# Adafruit_MPU6050.net
KiCad netlist of a schematic drawn in EAGLE
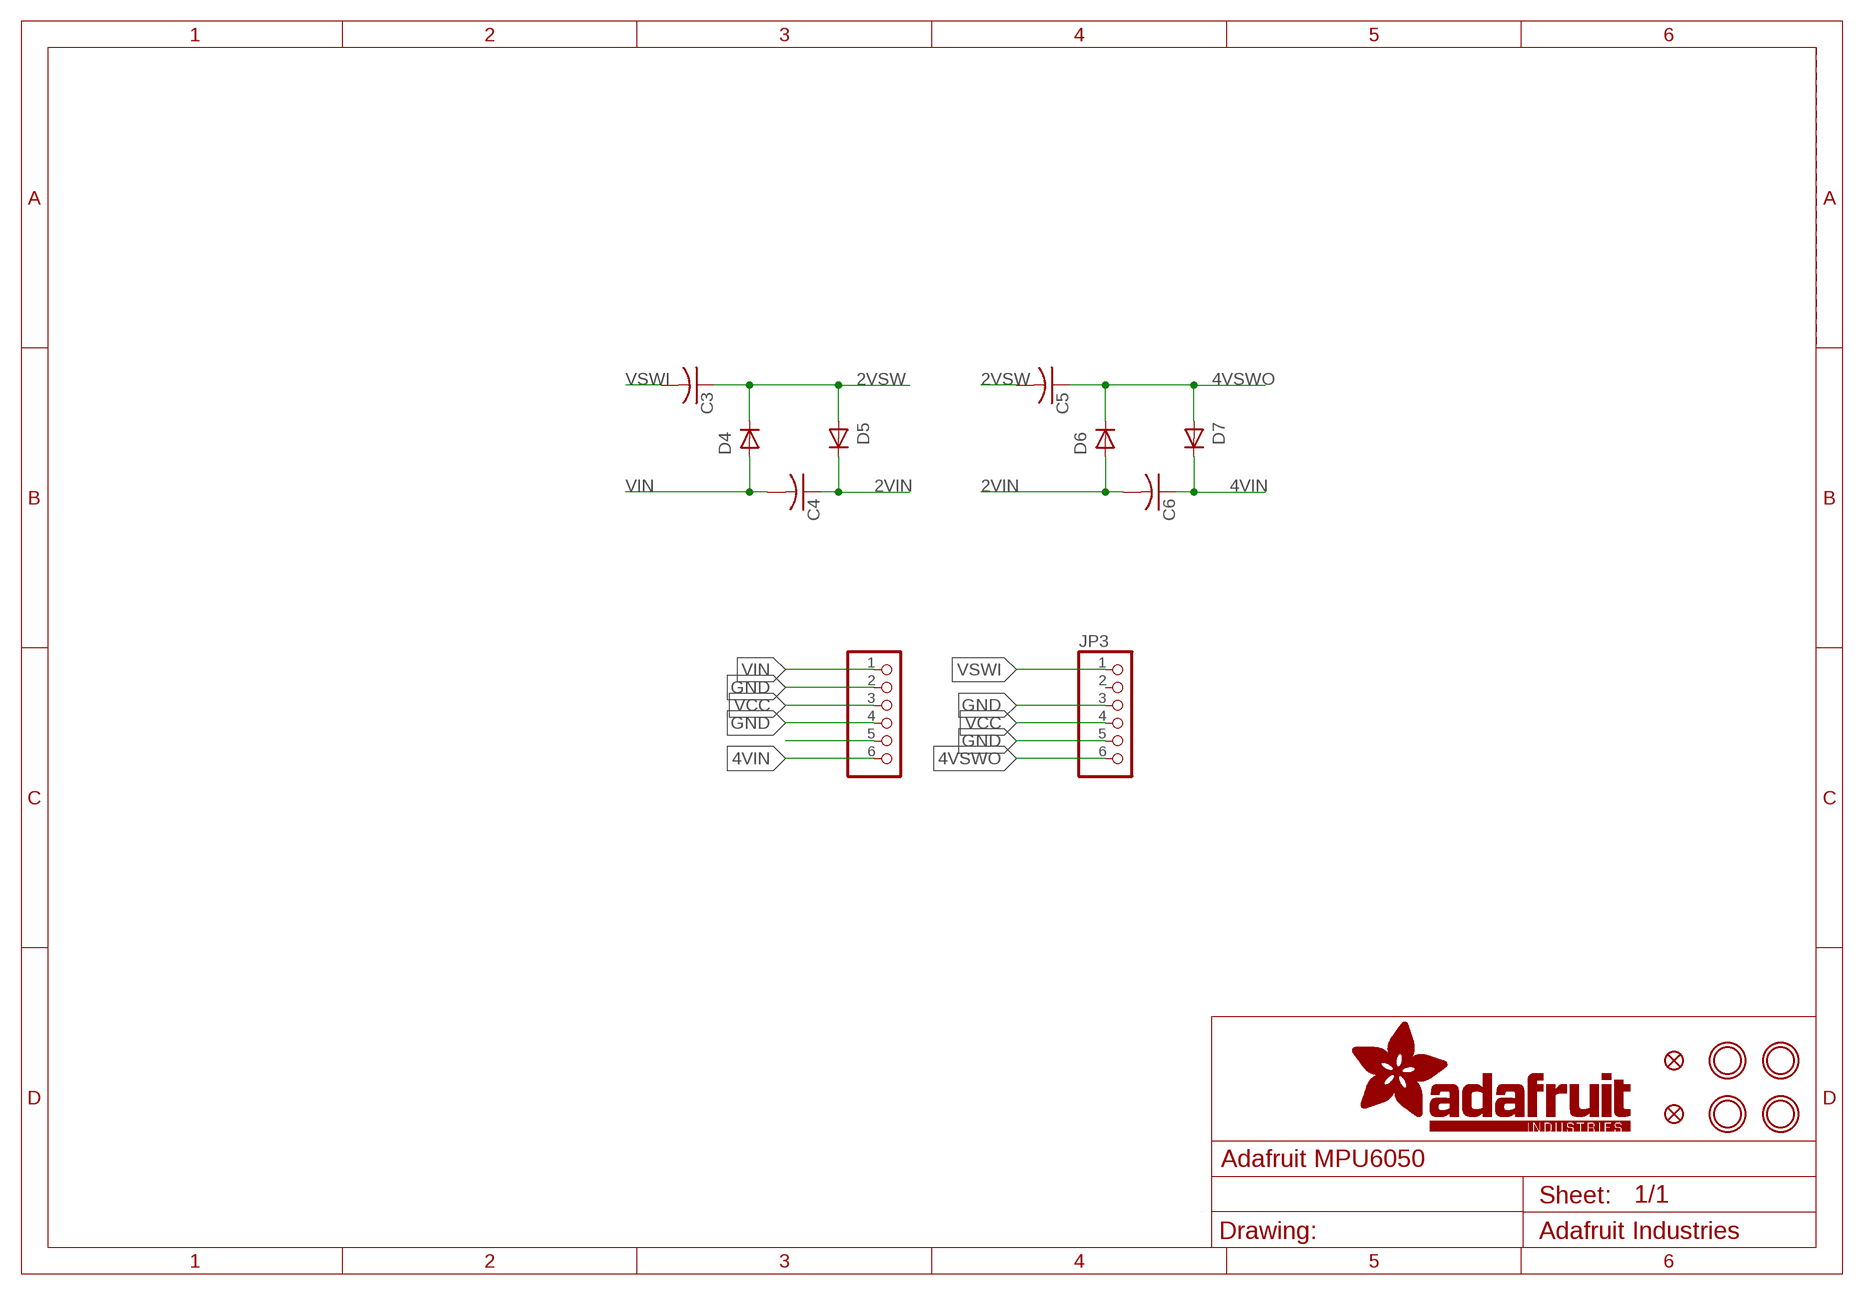
[diagram p0: schematic, sheet 1]

(export (version "E")
  (design (tool "Eeschema 10.0.6"))
  (components
    (comp (ref "C3")
      (value "C-USC0603")
      (footprint "eagle-import:C0603")
      (fields (field (name "MANUFACTURER") "?"))
      (libsource (lib "eagle-import") (part "C-USC0603"))
    )
    (comp (ref "C4")
      (value "C-USC0603")
      (footprint "eagle-import:C0603")
      (fields (field (name "MANUFACTURER") "?"))
      (libsource (lib "eagle-import") (part "C-USC0603"))
    )
    (comp (ref "C5")
      (value "C-USC0603")
      (footprint "eagle-import:C0603")
      (fields (field (name "MANUFACTURER") "?"))
      (libsource (lib "eagle-import") (part "C-USC0603"))
    )
    (comp (ref "C6")
      (value "C-USC0603")
      (footprint "eagle-import:C0603")
      (fields (field (name "MANUFACTURER") "?"))
      (libsource (lib "eagle-import") (part "C-USC0603"))
    )
    (comp (ref "D4")
      (value "DI-BAS21LD")
      (footprint "eagle-import:SOD882D")
      (fields
        (field (name "MANUFACTURER") "Nexperia")
        (field (name "PART_NUMBER") " BAS21LDYL")
        (field (name "TOLERANCE") "?")
      )
      (libsource (lib "eagle-import") (part "DI-BAS21LD"))
    )
    (comp (ref "D5")
      (value "DI-BAS21LD")
      (footprint "eagle-import:SOD882D")
      (fields
        (field (name "MANUFACTURER") "Nexperia")
        (field (name "PART_NUMBER") " BAS21LDYL")
        (field (name "TOLERANCE") "?")
      )
      (libsource (lib "eagle-import") (part "DI-BAS21LD"))
    )
    (comp (ref "D6")
      (value "DI-BAS21LD")
      (footprint "eagle-import:SOD882D")
      (fields
        (field (name "MANUFACTURER") "Nexperia")
        (field (name "PART_NUMBER") " BAS21LDYL")
        (field (name "TOLERANCE") "?")
      )
      (libsource (lib "eagle-import") (part "DI-BAS21LD"))
    )
    (comp (ref "D7")
      (value "DI-BAS21LD")
      (footprint "eagle-import:SOD882D")
      (fields
        (field (name "MANUFACTURER") "Nexperia")
        (field (name "PART_NUMBER") " BAS21LDYL")
        (field (name "TOLERANCE") "?")
      )
      (libsource (lib "eagle-import") (part "DI-BAS21LD"))
    )
    (comp (ref "FID3")
      (value "FIDUCIAL_1MM")
      (footprint "eagle-import:FIDUCIAL_1MM")
      (libsource (lib "eagle-import") (part "FIDUCIAL_1MM"))
    )
    (comp (ref "FID4")
      (value "FIDUCIAL_1MM")
      (footprint "eagle-import:FIDUCIAL_1MM")
      (libsource (lib "eagle-import") (part "FIDUCIAL_1MM"))
    )
    (comp (ref "JP2")
      (value "HEADER-1X6ROUND")
      (footprint "eagle-import:1X06_ROUND")
      (libsource (lib "eagle-import") (part "HEADER-1X6ROUND"))
    )
    (comp (ref "JP3")
      (value "HEADER-1X670MIL")
      (footprint "eagle-import:1X06_ROUND_70")
      (libsource (lib "eagle-import") (part "HEADER-1X670MIL"))
    )
    (comp (ref "U$39")
      (value "MOUNTINGHOLE2.5")
      (footprint "eagle-import:MOUNTINGHOLE_2.5_PLATED")
      (libsource (lib "eagle-import") (part "MOUNTINGHOLE2.5"))
    )
    (comp (ref "U$40")
      (value "MOUNTINGHOLE2.5")
      (footprint "eagle-import:MOUNTINGHOLE_2.5_PLATED")
      (libsource (lib "eagle-import") (part "MOUNTINGHOLE2.5"))
    )
    (comp (ref "U$42")
      (value "MOUNTINGHOLE2.5")
      (footprint "eagle-import:MOUNTINGHOLE_2.5_PLATED")
      (libsource (lib "eagle-import") (part "MOUNTINGHOLE2.5"))
    )
    (comp (ref "U$43")
      (value "MOUNTINGHOLE2.5")
      (footprint "eagle-import:MOUNTINGHOLE_2.5_PLATED")
      (libsource (lib "eagle-import") (part "MOUNTINGHOLE2.5"))
    )
  )
  (nets
    (net (code "1") (name "/2VIN") (class "Default")
      (node (ref "C4") (pin "1") (pinfunction "1_1") (pintype "passive"))
      (node (ref "C6") (pin "2") (pinfunction "2_2") (pintype "passive"))
      (node (ref "D5") (pin "K") (pinfunction "K_K") (pintype "passive"))
      (node (ref "D6") (pin "A") (pinfunction "A_A") (pintype "passive"))
    )
    (net (code "2") (name "/2VSW") (class "Default")
      (node (ref "C3") (pin "1") (pinfunction "1_1") (pintype "passive"))
      (node (ref "C5") (pin "2") (pinfunction "2_2") (pintype "passive"))
      (node (ref "D4") (pin "K") (pinfunction "K_K") (pintype "passive"))
      (node (ref "D5") (pin "A") (pinfunction "A_A") (pintype "passive"))
    )
    (net (code "3") (name "4VIN") (class "Default")
      (node (ref "C6") (pin "1") (pinfunction "1_1") (pintype "passive"))
      (node (ref "D7") (pin "K") (pinfunction "K_K") (pintype "passive"))
      (node (ref "JP2") (pin "6") (pinfunction "6_6") (pintype "passive"))
    )
    (net (code "4") (name "4VSWO") (class "Default")
      (node (ref "C5") (pin "1") (pinfunction "1_1") (pintype "passive"))
      (node (ref "D6") (pin "K") (pinfunction "K_K") (pintype "passive"))
      (node (ref "D7") (pin "A") (pinfunction "A_A") (pintype "passive"))
      (node (ref "JP3") (pin "6") (pinfunction "6_6") (pintype "passive"))
    )
    (net (code "5") (name "GND") (class "Default")
      (node (ref "JP2") (pin "2") (pinfunction "2_2") (pintype "passive"))
      (node (ref "JP2") (pin "4") (pinfunction "4_4") (pintype "passive"))
      (node (ref "JP3") (pin "3") (pinfunction "3_3") (pintype "passive"))
      (node (ref "JP3") (pin "5") (pinfunction "5_5") (pintype "passive"))
    )
    (net (code "6") (name "VCC") (class "Default")
      (node (ref "JP2") (pin "3") (pinfunction "3_3") (pintype "passive"))
      (node (ref "JP3") (pin "4") (pinfunction "4_4") (pintype "passive"))
    )
    (net (code "7") (name "VIN") (class "Default")
      (node (ref "C4") (pin "2") (pinfunction "2_2") (pintype "passive"))
      (node (ref "D4") (pin "A") (pinfunction "A_A") (pintype "passive"))
      (node (ref "JP2") (pin "1") (pinfunction "1_1") (pintype "passive"))
    )
    (net (code "8") (name "VSWI") (class "Default")
      (node (ref "C3") (pin "2") (pinfunction "2_2") (pintype "passive"))
      (node (ref "JP3") (pin "1") (pinfunction "1_1") (pintype "passive"))
    )
    (net (code "9") (name "unconnected-(JP2-Pad5)") (class "Default")
      (node (ref "JP2") (pin "5") (pinfunction "5_5") (pintype "passive"))
    )
    (net (code "10") (name "unconnected-(JP3-Pad2)") (class "Default")
      (node (ref "JP3") (pin "2") (pinfunction "2_2") (pintype "passive"))
    )
  )
)
